# GPIO.net
KiCad netlist of a schematic drawn in Altium Designer
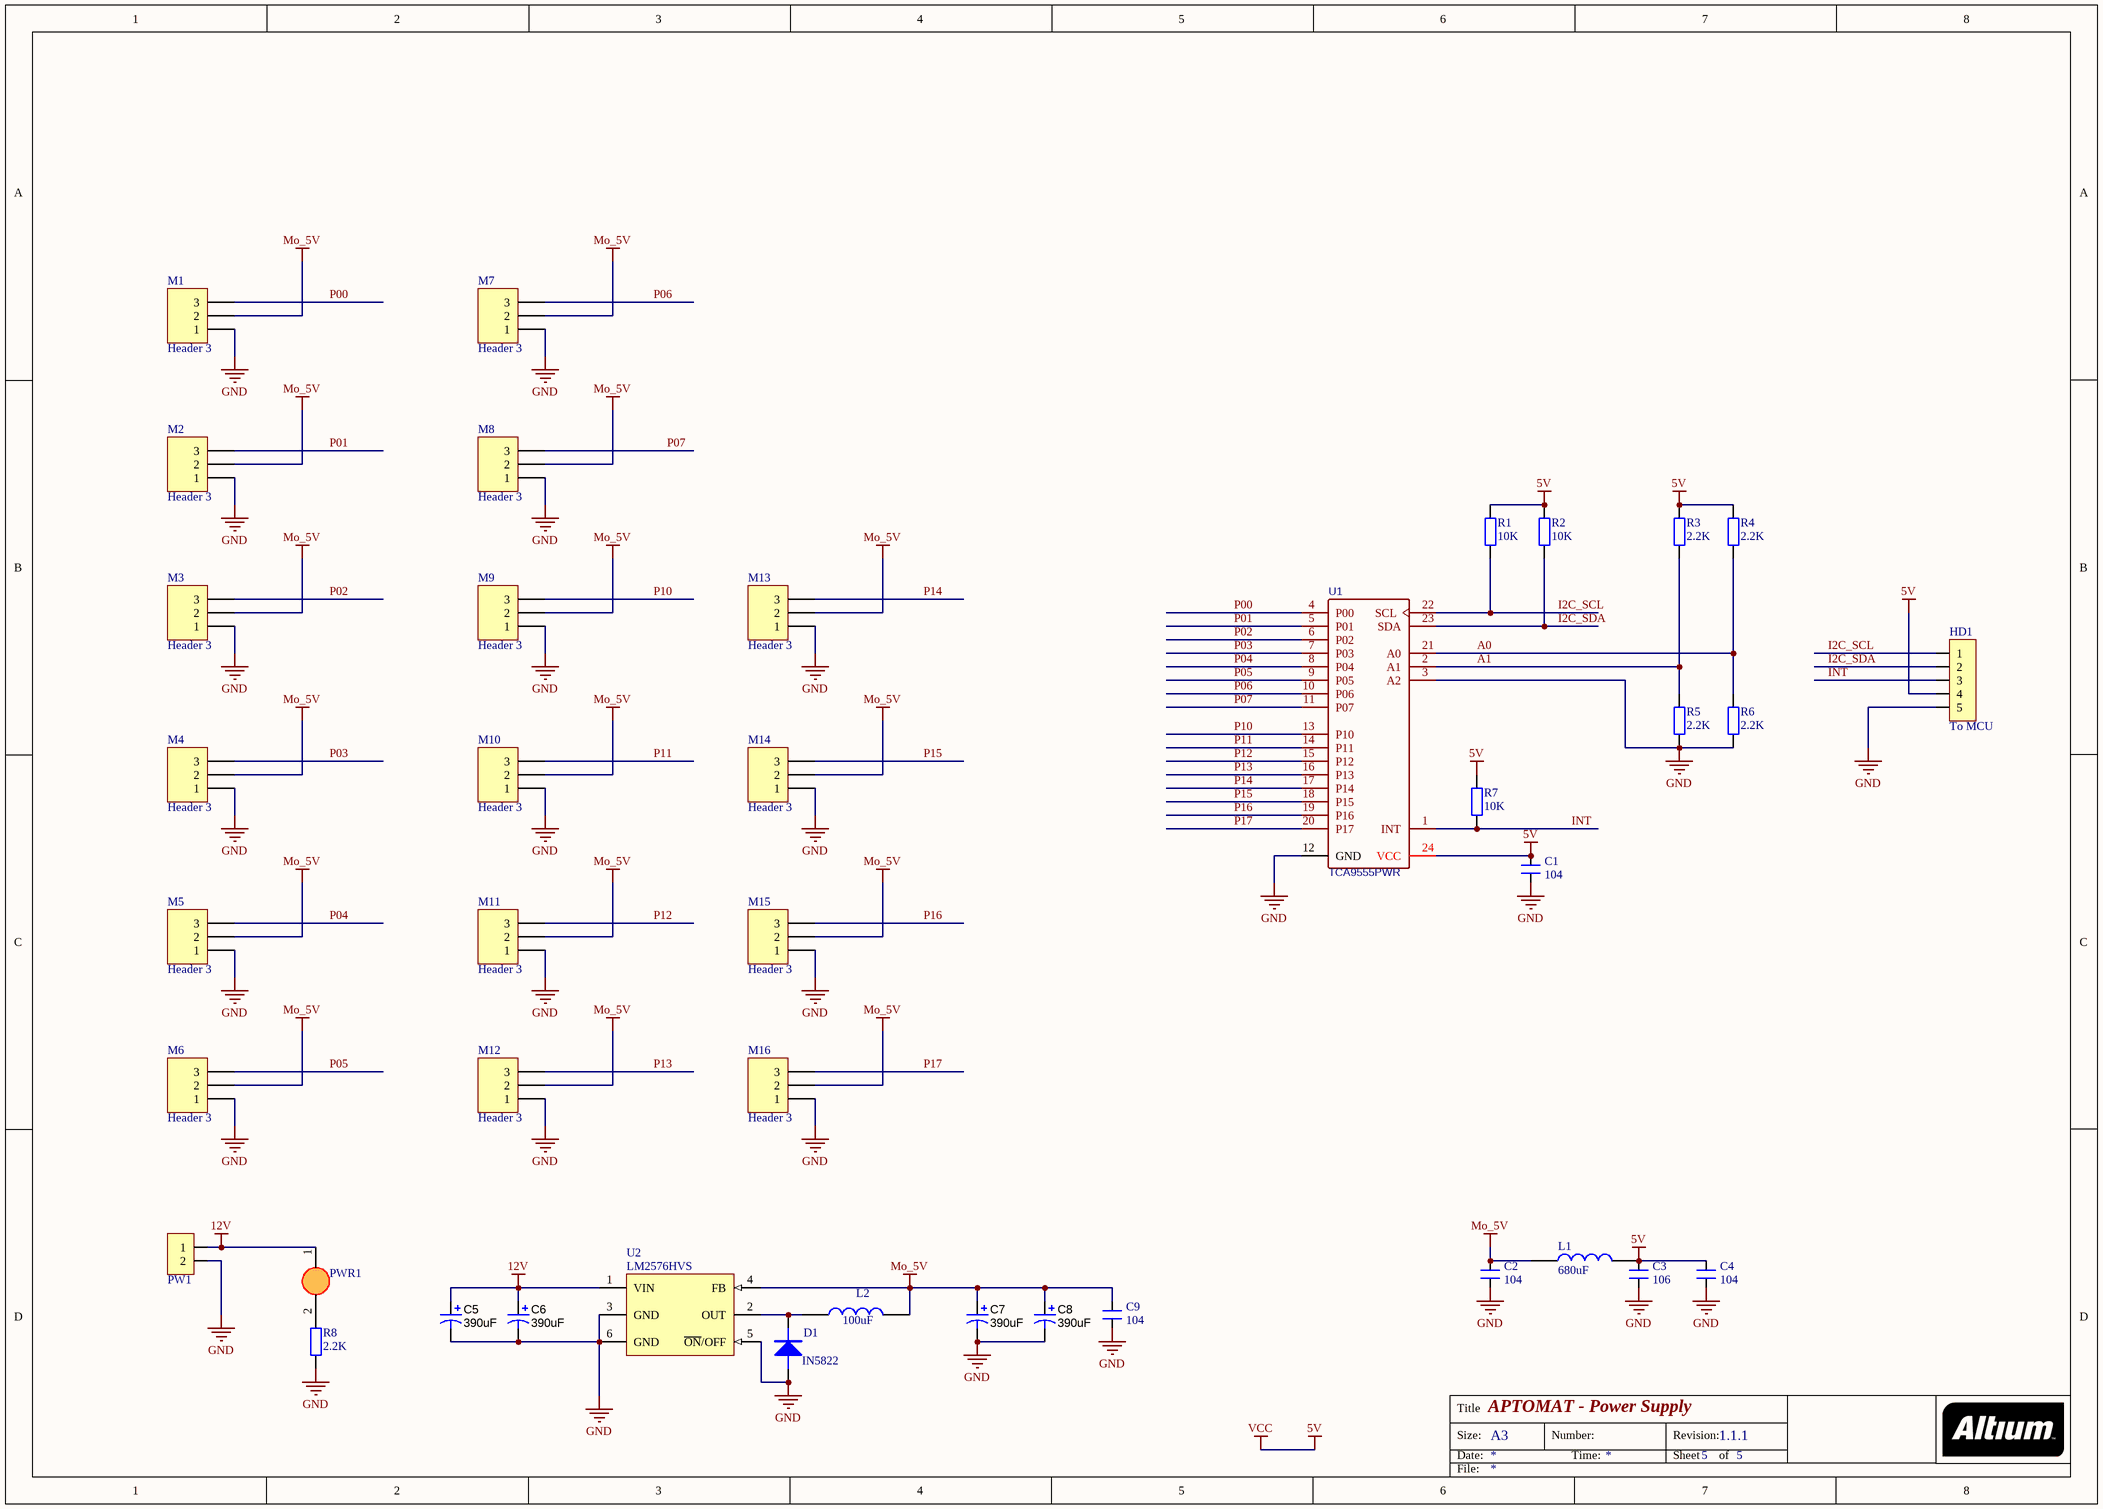
[diagram p0: GPIO.SchDoc]

(export (version "E")
  (design (tool "Eeschema 10.0.6"))
  (components
    (comp (ref "C1")
      (value "104")
      (footprint "0805_HV")
      (description "Cap SMD")
      (libsource (lib "hatcatbietbay") (part "CM"))
    )
    (comp (ref "C2")
      (value "104")
      (footprint "0805_HV")
      (description "Cap SMD")
      (libsource (lib "hatcatbietbay") (part "CM"))
    )
    (comp (ref "C3")
      (value "106")
      (footprint "0805_HV")
      (description "Cap SMD")
      (libsource (lib "hatcatbietbay") (part "CM"))
    )
    (comp (ref "C4")
      (value "104")
      (footprint "0805_HV")
      (description "Cap SMD")
      (libsource (lib "hatcatbietbay") (part "CM"))
    )
    (comp (ref "C5")
      (value "390uF")
      (footprint "CP1/3.0")
      (fields
        (field (name "PARTNUMBER") "UHW1H391MPD6")
        (field (name "MANUFACTURER") "Nichicon")
        (field (name "VALUEDISPLAYED") "390uF")
        (field (name "PUBLISHER") "Texas Instruments")
      )
      (libsource (lib "mySch") (part "Capacitor TuHoa"))
    )
    (comp (ref "C6")
      (value "390uF")
      (footprint "CP1/3.0")
      (fields
        (field (name "PARTNUMBER") "UHW1H391MPD6")
        (field (name "MANUFACTURER") "Nichicon")
        (field (name "VALUEDISPLAYED") "390uF")
        (field (name "PUBLISHER") "Texas Instruments")
      )
      (libsource (lib "mySch") (part "Capacitor TuHoa"))
    )
    (comp (ref "C7")
      (value "390uF")
      (footprint "CP1/3.0")
      (fields
        (field (name "PARTNUMBER") "UHW1H391MPD6")
        (field (name "MANUFACTURER") "Nichicon")
        (field (name "VALUEDISPLAYED") "390uF")
        (field (name "PUBLISHER") "Texas Instruments")
      )
      (libsource (lib "mySch") (part "Capacitor TuHoa"))
    )
    (comp (ref "C8")
      (value "390uF")
      (footprint "CP1/3.0")
      (fields
        (field (name "PARTNUMBER") "UHW1H391MPD6")
        (field (name "MANUFACTURER") "Nichicon")
        (field (name "VALUEDISPLAYED") "390uF")
        (field (name "PUBLISHER") "Texas Instruments")
      )
      (libsource (lib "mySch") (part "Capacitor TuHoa"))
    )
    (comp (ref "C9")
      (value "104")
      (footprint "0805_HV")
      (description "Cap SMD")
      (libsource (lib "hatcatbietbay") (part "CM"))
    )
    (comp (ref "D1")
      (value "IN5822")
      (footprint "SOD123")
      (description "Diode S4 SOD123 ( 1N5819 SOD123)")
      (libsource (lib "MH_DA_THU_VIEN_16122016") (part "Diode S4 SOD123 ( 1N5819 SOD123)_MH"))
    )
    (comp (ref "HD1")
      (value "To MCU")
      (footprint "HEADER 5")
      (description "Header 5P XH2.54 thẳng")
      (libsource (lib "MH_DA_THU_VIEN_16122016") (part "Header 5_MH"))
    )
    (comp (ref "L1")
      (value "680uF")
      (footprint "Inductor 4.5x5")
      (libsource (lib "MH_DA_THU_VIEN_16122016") (part "Inductor 4.5x5_MH"))
    )
    (comp (ref "L2")
      (value "100uF")
      (footprint "IND_2118-V-RC")
      (description "cuon cam")
      (libsource (lib "MH_DA_THU_VIEN_16122016") (part "Inductor Lm2576_MH"))
    )
    (comp (ref "M1")
      (value "Header 3")
      (footprint "HDR1X3")
      (description "Header, 3-Pin")
      (fields (field (name "PUBLISHER") "Altium Limited"))
      (libsource (lib "Miscellaneous Connectors") (part "Header 3"))
    )
    (comp (ref "M2")
      (value "Header 3")
      (footprint "HDR1X3")
      (description "Header, 3-Pin")
      (fields (field (name "PUBLISHER") "Altium Limited"))
      (libsource (lib "Miscellaneous Connectors") (part "Header 3"))
    )
    (comp (ref "M3")
      (value "Header 3")
      (footprint "HDR1X3")
      (description "Header, 3-Pin")
      (fields (field (name "PUBLISHER") "Altium Limited"))
      (libsource (lib "Miscellaneous Connectors") (part "Header 3"))
    )
    (comp (ref "M4")
      (value "Header 3")
      (footprint "HDR1X3")
      (description "Header, 3-Pin")
      (fields (field (name "PUBLISHER") "Altium Limited"))
      (libsource (lib "Miscellaneous Connectors") (part "Header 3"))
    )
    (comp (ref "M5")
      (value "Header 3")
      (footprint "HDR1X3")
      (description "Header, 3-Pin")
      (fields (field (name "PUBLISHER") "Altium Limited"))
      (libsource (lib "Miscellaneous Connectors") (part "Header 3"))
    )
    (comp (ref "M6")
      (value "Header 3")
      (footprint "HDR1X3")
      (description "Header, 3-Pin")
      (fields (field (name "PUBLISHER") "Altium Limited"))
      (libsource (lib "Miscellaneous Connectors") (part "Header 3"))
    )
    (comp (ref "M7")
      (value "Header 3")
      (footprint "HDR1X3")
      (description "Header, 3-Pin")
      (fields (field (name "PUBLISHER") "Altium Limited"))
      (libsource (lib "Miscellaneous Connectors") (part "Header 3"))
    )
    (comp (ref "M8")
      (value "Header 3")
      (footprint "HDR1X3")
      (description "Header, 3-Pin")
      (fields (field (name "PUBLISHER") "Altium Limited"))
      (libsource (lib "Miscellaneous Connectors") (part "Header 3"))
    )
    (comp (ref "M9")
      (value "Header 3")
      (footprint "HDR1X3")
      (description "Header, 3-Pin")
      (fields (field (name "PUBLISHER") "Altium Limited"))
      (libsource (lib "Miscellaneous Connectors") (part "Header 3"))
    )
    (comp (ref "M10")
      (value "Header 3")
      (footprint "HDR1X3")
      (description "Header, 3-Pin")
      (fields (field (name "PUBLISHER") "Altium Limited"))
      (libsource (lib "Miscellaneous Connectors") (part "Header 3"))
    )
    (comp (ref "M11")
      (value "Header 3")
      (footprint "HDR1X3")
      (description "Header, 3-Pin")
      (fields (field (name "PUBLISHER") "Altium Limited"))
      (libsource (lib "Miscellaneous Connectors") (part "Header 3"))
    )
    (comp (ref "M12")
      (value "Header 3")
      (footprint "HDR1X3")
      (description "Header, 3-Pin")
      (fields (field (name "PUBLISHER") "Altium Limited"))
      (libsource (lib "Miscellaneous Connectors") (part "Header 3"))
    )
    (comp (ref "M13")
      (value "Header 3")
      (footprint "HDR1X3")
      (description "Header, 3-Pin")
      (fields (field (name "PUBLISHER") "Altium Limited"))
      (libsource (lib "Miscellaneous Connectors") (part "Header 3"))
    )
    (comp (ref "M14")
      (value "Header 3")
      (footprint "HDR1X3")
      (description "Header, 3-Pin")
      (fields (field (name "PUBLISHER") "Altium Limited"))
      (libsource (lib "Miscellaneous Connectors") (part "Header 3"))
    )
    (comp (ref "M15")
      (value "Header 3")
      (footprint "HDR1X3")
      (description "Header, 3-Pin")
      (fields (field (name "PUBLISHER") "Altium Limited"))
      (libsource (lib "Miscellaneous Connectors") (part "Header 3"))
    )
    (comp (ref "M16")
      (value "Header 3")
      (footprint "HDR1X3")
      (description "Header, 3-Pin")
      (fields (field (name "PUBLISHER") "Altium Limited"))
      (libsource (lib "Miscellaneous Connectors") (part "Header 3"))
    )
    (comp (ref "PW1")
      (value "CON 2 EDG 5.08_MH")
      (footprint "CON 2 EDG 5.08")
      (description "CON 2 EDG 5.08 (xanh cong)")
      (libsource (lib "MH_DA_THU_VIEN_16122016") (part "CON 2 EDG 5.08_MH"))
    )
    (comp (ref "PWR1")
      (value "LED3")
      (footprint "LED_0805")
      (description "LED 3mm")
      (libsource (lib "MH_DA_THU_VIEN_16122016") (part "LED SMD_0805_MH"))
    )
    (comp (ref "R1")
      (value "10K")
      (footprint "0805_HV")
      (description "TRO_SMD_0805_MH")
      (libsource (lib "MH_DA_THU_VIEN_16122016") (part "TRO_SMD_0805_MH"))
    )
    (comp (ref "R2")
      (value "10K")
      (footprint "0805_HV")
      (description "TRO_SMD_0805_MH")
      (libsource (lib "MH_DA_THU_VIEN_16122016") (part "TRO_SMD_0805_MH"))
    )
    (comp (ref "R3")
      (value "2.2K")
      (footprint "0805_HV")
      (description "TRO_SMD_0805_MH")
      (libsource (lib "MH_DA_THU_VIEN_16122016") (part "TRO_SMD_0805_MH"))
    )
    (comp (ref "R4")
      (value "2.2K")
      (footprint "0805_HV")
      (description "TRO_SMD_0805_MH")
      (libsource (lib "MH_DA_THU_VIEN_16122016") (part "TRO_SMD_0805_MH"))
    )
    (comp (ref "R5")
      (value "2.2K")
      (footprint "0805_HV")
      (description "TRO_SMD_0805_MH")
      (libsource (lib "MH_DA_THU_VIEN_16122016") (part "TRO_SMD_0805_MH"))
    )
    (comp (ref "R6")
      (value "2.2K")
      (footprint "0805_HV")
      (description "TRO_SMD_0805_MH")
      (libsource (lib "MH_DA_THU_VIEN_16122016") (part "TRO_SMD_0805_MH"))
    )
    (comp (ref "R7")
      (value "10K")
      (footprint "0805_HV")
      (description "TRO_SMD_0805_MH")
      (libsource (lib "MH_DA_THU_VIEN_16122016") (part "TRO_SMD_0805_MH"))
    )
    (comp (ref "R8")
      (value "2.2K")
      (footprint "MH_DA_THU_VIEN_16122016:Tro SMD 0805")
      (description "TRO_SMD_0805_MH")
      (libsource (lib "MH_DA_THU_VIEN_16122016") (part "TRO_SMD_0805_MH"))
    )
    (comp (ref "U1")
      (value "TCA9555PWR")
      (footprint "TSSOP-24")
      (fields (field (name "BOM_MANUFACTURER PART") "?"))
      (libsource (lib "Schlib1") (part "TCA9555PWR"))
    )
    (comp (ref "U2")
      (value "LM2576HVS")
      (footprint "TO263-5")
      (description "LM2576HVS-5.0V BUCK 5V 3A TO263-5 _MH")
      (fields
        (field (name "PARTNUMBER") "LM2576T-5.0")
        (field (name "MANUFACTURER") "National Semiconductor")
        (field (name "PUBLISHER") "Altium Limited")
      )
      (libsource (lib "MH_DA_THU_VIEN_16122016") (part "LM2576HVS-5.0V BUCK 5V 3A TO263-5 _MH"))
    )
  )
  (nets
    (net (code "1") (name "/A0") (class "Default")
      (node (ref "R4") (pin "1") (pinfunction "1_1") (pintype "passive"))
      (node (ref "R6") (pin "2") (pinfunction "2_2") (pintype "passive"))
      (node (ref "U1") (pin "21") (pinfunction "A0_21") (pintype "passive"))
    )
    (net (code "2") (name "/A1") (class "Default")
      (node (ref "R3") (pin "1") (pinfunction "1_1") (pintype "passive"))
      (node (ref "R5") (pin "2") (pinfunction "2_2") (pintype "passive"))
      (node (ref "U1") (pin "2") (pinfunction "A1_2") (pintype "passive"))
    )
    (net (code "3") (name "/I2C_SCL") (class "Default")
      (node (ref "HD1") (pin "1") (pinfunction "1_1") (pintype "passive"))
      (node (ref "R1") (pin "1") (pinfunction "1_1") (pintype "passive"))
      (node (ref "U1") (pin "22") (pinfunction "SCL_22") (pintype "passive"))
    )
    (net (code "4") (name "/I2C_SDA") (class "Default")
      (node (ref "HD1") (pin "2") (pinfunction "2_2") (pintype "passive"))
      (node (ref "R2") (pin "1") (pinfunction "1_1") (pintype "passive"))
      (node (ref "U1") (pin "23") (pinfunction "SDA_23") (pintype "passive"))
    )
    (net (code "5") (name "/INT") (class "Default")
      (node (ref "HD1") (pin "3") (pinfunction "3_3") (pintype "passive"))
      (node (ref "R7") (pin "1") (pinfunction "1_1") (pintype "passive"))
      (node (ref "U1") (pin "1") (pinfunction "INT_1") (pintype "passive"))
    )
    (net (code "6") (name "/P00") (class "Default")
      (node (ref "M1") (pin "3") (pinfunction "3_3") (pintype "passive"))
      (node (ref "U1") (pin "4") (pinfunction "P00_4") (pintype "passive"))
    )
    (net (code "7") (name "/P01") (class "Default")
      (node (ref "M2") (pin "3") (pinfunction "3_3") (pintype "passive"))
      (node (ref "U1") (pin "5") (pinfunction "P01_5") (pintype "passive"))
    )
    (net (code "8") (name "/P02") (class "Default")
      (node (ref "M3") (pin "3") (pinfunction "3_3") (pintype "passive"))
      (node (ref "U1") (pin "6") (pinfunction "P02_6") (pintype "passive"))
    )
    (net (code "9") (name "/P03") (class "Default")
      (node (ref "M4") (pin "3") (pinfunction "3_3") (pintype "passive"))
      (node (ref "U1") (pin "7") (pinfunction "P03_7") (pintype "passive"))
    )
    (net (code "10") (name "/P04") (class "Default")
      (node (ref "M5") (pin "3") (pinfunction "3_3") (pintype "passive"))
      (node (ref "U1") (pin "8") (pinfunction "P04_8") (pintype "passive"))
    )
    (net (code "11") (name "/P05") (class "Default")
      (node (ref "M6") (pin "3") (pinfunction "3_3") (pintype "passive"))
      (node (ref "U1") (pin "9") (pinfunction "P05_9") (pintype "passive"))
    )
    (net (code "12") (name "/P06") (class "Default")
      (node (ref "M7") (pin "3") (pinfunction "3_3") (pintype "passive"))
      (node (ref "U1") (pin "10") (pinfunction "P06_10") (pintype "passive"))
    )
    (net (code "13") (name "/P07") (class "Default")
      (node (ref "M8") (pin "3") (pinfunction "3_3") (pintype "passive"))
      (node (ref "U1") (pin "11") (pinfunction "P07_11") (pintype "passive"))
    )
    (net (code "14") (name "/P10") (class "Default")
      (node (ref "M9") (pin "3") (pinfunction "3_3") (pintype "passive"))
      (node (ref "U1") (pin "13") (pinfunction "P10_13") (pintype "passive"))
    )
    (net (code "15") (name "/P11") (class "Default")
      (node (ref "M10") (pin "3") (pinfunction "3_3") (pintype "passive"))
      (node (ref "U1") (pin "14") (pinfunction "P11_14") (pintype "passive"))
    )
    (net (code "16") (name "/P12") (class "Default")
      (node (ref "M11") (pin "3") (pinfunction "3_3") (pintype "passive"))
      (node (ref "U1") (pin "15") (pinfunction "P12_15") (pintype "passive"))
    )
    (net (code "17") (name "/P13") (class "Default")
      (node (ref "M12") (pin "3") (pinfunction "3_3") (pintype "passive"))
      (node (ref "U1") (pin "16") (pinfunction "P13_16") (pintype "passive"))
    )
    (net (code "18") (name "/P14") (class "Default")
      (node (ref "M13") (pin "3") (pinfunction "3_3") (pintype "passive"))
      (node (ref "U1") (pin "17") (pinfunction "P14_17") (pintype "passive"))
    )
    (net (code "19") (name "/P15") (class "Default")
      (node (ref "M14") (pin "3") (pinfunction "3_3") (pintype "passive"))
      (node (ref "U1") (pin "18") (pinfunction "P15_18") (pintype "passive"))
    )
    (net (code "20") (name "/P16") (class "Default")
      (node (ref "M15") (pin "3") (pinfunction "3_3") (pintype "passive"))
      (node (ref "U1") (pin "19") (pinfunction "P16_19") (pintype "passive"))
    )
    (net (code "21") (name "/P17") (class "Default")
      (node (ref "M16") (pin "3") (pinfunction "3_3") (pintype "passive"))
      (node (ref "U1") (pin "20") (pinfunction "P17_20") (pintype "passive"))
    )
    (net (code "22") (name "5V") (class "Default")
      (node (ref "C1") (pin "2") (pinfunction "2_2") (pintype "passive"))
      (node (ref "C3") (pin "2") (pinfunction "2_2") (pintype "passive"))
      (node (ref "C4") (pin "2") (pinfunction "2_2") (pintype "passive"))
      (node (ref "HD1") (pin "4") (pinfunction "4_4") (pintype "passive"))
      (node (ref "L1") (pin "2") (pinfunction "2_2") (pintype "passive"))
      (node (ref "R1") (pin "2") (pinfunction "2_2") (pintype "passive"))
      (node (ref "R2") (pin "2") (pinfunction "2_2") (pintype "passive"))
      (node (ref "R3") (pin "2") (pinfunction "2_2") (pintype "passive"))
      (node (ref "R4") (pin "2") (pinfunction "2_2") (pintype "passive"))
      (node (ref "R7") (pin "2") (pinfunction "2_2") (pintype "passive"))
      (node (ref "U1") (pin "24") (pinfunction "VCC_24") (pintype "passive"))
    )
    (net (code "23") (name "12V") (class "Default")
      (node (ref "C5") (pin "1") (pinfunction "+_1") (pintype "passive"))
      (node (ref "C6") (pin "1") (pinfunction "+_1") (pintype "passive"))
      (node (ref "PW1") (pin "1") (pinfunction "1_1") (pintype "passive"))
      (node (ref "PWR1") (pin "1") (pinfunction "A_1") (pintype "passive"))
      (node (ref "U2") (pin "1") (pinfunction "VIN_1") (pintype "power_in"))
    )
    (net (code "24") (name "GND") (class "Default")
      (node (ref "C1") (pin "1") (pinfunction "1_1") (pintype "passive"))
      (node (ref "C2") (pin "1") (pinfunction "1_1") (pintype "passive"))
      (node (ref "C3") (pin "1") (pinfunction "1_1") (pintype "passive"))
      (node (ref "C4") (pin "1") (pinfunction "1_1") (pintype "passive"))
      (node (ref "C5") (pin "2") (pinfunction "-_2") (pintype "passive"))
      (node (ref "C6") (pin "2") (pinfunction "-_2") (pintype "passive"))
      (node (ref "C7") (pin "2") (pinfunction "-_2") (pintype "passive"))
      (node (ref "C8") (pin "2") (pinfunction "-_2") (pintype "passive"))
      (node (ref "C9") (pin "1") (pinfunction "1_1") (pintype "passive"))
      (node (ref "D1") (pin "1") (pinfunction "1_1") (pintype "passive"))
      (node (ref "HD1") (pin "5") (pinfunction "5_5") (pintype "passive"))
      (node (ref "M1") (pin "1") (pinfunction "1_1") (pintype "passive"))
      (node (ref "M10") (pin "1") (pinfunction "1_1") (pintype "passive"))
      (node (ref "M11") (pin "1") (pinfunction "1_1") (pintype "passive"))
      (node (ref "M12") (pin "1") (pinfunction "1_1") (pintype "passive"))
      (node (ref "M13") (pin "1") (pinfunction "1_1") (pintype "passive"))
      (node (ref "M14") (pin "1") (pinfunction "1_1") (pintype "passive"))
      (node (ref "M15") (pin "1") (pinfunction "1_1") (pintype "passive"))
      (node (ref "M16") (pin "1") (pinfunction "1_1") (pintype "passive"))
      (node (ref "M2") (pin "1") (pinfunction "1_1") (pintype "passive"))
      (node (ref "M3") (pin "1") (pinfunction "1_1") (pintype "passive"))
      (node (ref "M4") (pin "1") (pinfunction "1_1") (pintype "passive"))
      (node (ref "M5") (pin "1") (pinfunction "1_1") (pintype "passive"))
      (node (ref "M6") (pin "1") (pinfunction "1_1") (pintype "passive"))
      (node (ref "M7") (pin "1") (pinfunction "1_1") (pintype "passive"))
      (node (ref "M8") (pin "1") (pinfunction "1_1") (pintype "passive"))
      (node (ref "M9") (pin "1") (pinfunction "1_1") (pintype "passive"))
      (node (ref "PW1") (pin "2") (pinfunction "2_2") (pintype "passive"))
      (node (ref "R5") (pin "1") (pinfunction "1_1") (pintype "passive"))
      (node (ref "R6") (pin "1") (pinfunction "1_1") (pintype "passive"))
      (node (ref "R8") (pin "1") (pinfunction "1_1") (pintype "passive"))
      (node (ref "U1") (pin "12") (pinfunction "GND_12") (pintype "passive"))
      (node (ref "U1") (pin "3") (pinfunction "A2_3") (pintype "passive"))
      (node (ref "U2") (pin "3") (pinfunction "GND_3") (pintype "power_in"))
      (node (ref "U2") (pin "5") (pinfunction "~{ON}/OFF_5") (pintype "input"))
      (node (ref "U2") (pin "6") (pinfunction "GND_6") (pintype "passive"))
    )
    (net (code "25") (name "Mo_5V") (class "Default")
      (node (ref "C2") (pin "2") (pinfunction "2_2") (pintype "passive"))
      (node (ref "C7") (pin "1") (pinfunction "+_1") (pintype "passive"))
      (node (ref "C8") (pin "1") (pinfunction "+_1") (pintype "passive"))
      (node (ref "C9") (pin "2") (pinfunction "2_2") (pintype "passive"))
      (node (ref "L1") (pin "1") (pinfunction "1_1") (pintype "passive"))
      (node (ref "L2") (pin "2") (pinfunction "2_2") (pintype "passive"))
      (node (ref "M1") (pin "2") (pinfunction "2_2") (pintype "passive"))
      (node (ref "M10") (pin "2") (pinfunction "2_2") (pintype "passive"))
      (node (ref "M11") (pin "2") (pinfunction "2_2") (pintype "passive"))
      (node (ref "M12") (pin "2") (pinfunction "2_2") (pintype "passive"))
      (node (ref "M13") (pin "2") (pinfunction "2_2") (pintype "passive"))
      (node (ref "M14") (pin "2") (pinfunction "2_2") (pintype "passive"))
      (node (ref "M15") (pin "2") (pinfunction "2_2") (pintype "passive"))
      (node (ref "M16") (pin "2") (pinfunction "2_2") (pintype "passive"))
      (node (ref "M2") (pin "2") (pinfunction "2_2") (pintype "passive"))
      (node (ref "M3") (pin "2") (pinfunction "2_2") (pintype "passive"))
      (node (ref "M4") (pin "2") (pinfunction "2_2") (pintype "passive"))
      (node (ref "M5") (pin "2") (pinfunction "2_2") (pintype "passive"))
      (node (ref "M6") (pin "2") (pinfunction "2_2") (pintype "passive"))
      (node (ref "M7") (pin "2") (pinfunction "2_2") (pintype "passive"))
      (node (ref "M8") (pin "2") (pinfunction "2_2") (pintype "passive"))
      (node (ref "M9") (pin "2") (pinfunction "2_2") (pintype "passive"))
      (node (ref "U2") (pin "4") (pinfunction "FB_4") (pintype "input"))
    )
    (net (code "26") (name "Net-(PWR1-K)") (class "Default")
      (node (ref "PWR1") (pin "2") (pinfunction "K_2") (pintype "passive"))
      (node (ref "R8") (pin "2") (pinfunction "2_2") (pintype "passive"))
    )
    (net (code "27") (name "Net-(U2-OUT)") (class "Default")
      (node (ref "D1") (pin "2") (pinfunction "2_2") (pintype "passive"))
      (node (ref "L2") (pin "1") (pinfunction "1_1") (pintype "passive"))
      (node (ref "U2") (pin "2") (pinfunction "OUT_2") (pintype "power_in"))
    )
  )
)
